# 09_LMS2_RF.net
KiCad netlist of a schematic drawn in Altium Designer
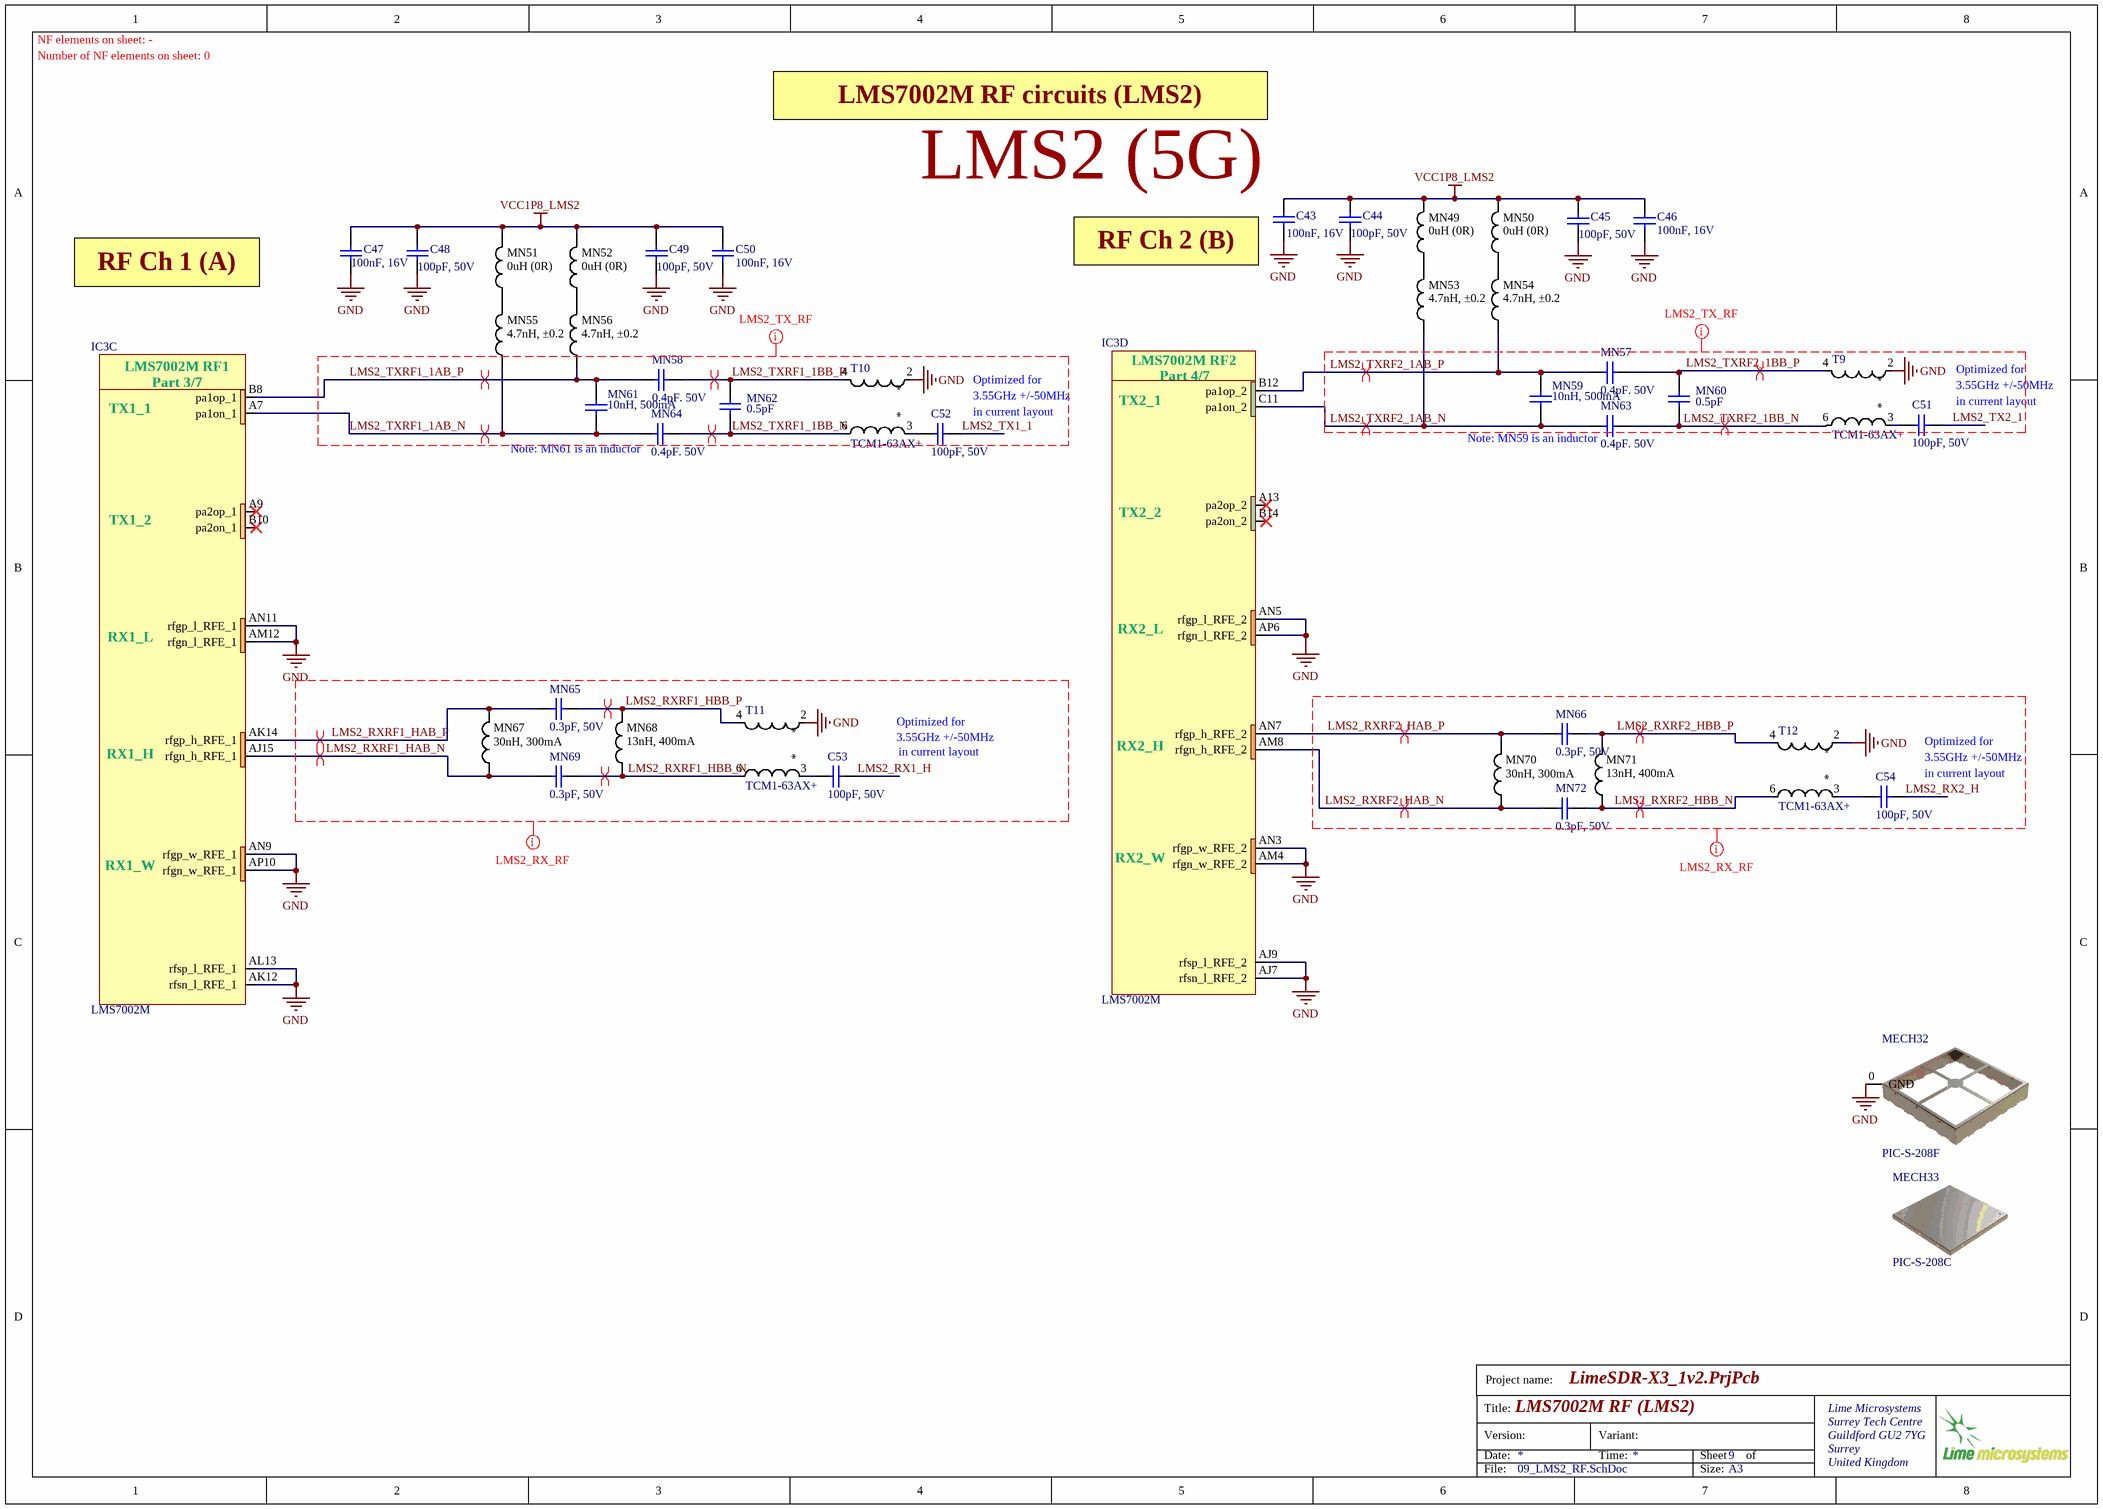
[diagram p0: 09_LMS2_RF.SchDoc]

(export (version "E")
  (design (tool "Eeschema 10.0.6"))
  (components
    (comp (ref "C43")
      (value "100nF, 16V")
      (footprint "CAP0402")
      (fields (field (name "MANUFACTURER") "Murata Electronics") (field (name "TOLERANCE") "10 %"))
      (libsource (lib "") (part "Cap_0402_7"))
    )
    (comp (ref "C44")
      (value "100pF, 50V")
      (footprint "CAP0402")
      (fields (field (name "MANUFACTURER") "Yageo") (field (name "TOLERANCE") "±5%"))
      (libsource (lib "") (part "Cap_0402_5"))
    )
    (comp (ref "C45")
      (value "100pF, 50V")
      (footprint "CAP0402")
      (fields (field (name "MANUFACTURER") "Yageo") (field (name "TOLERANCE") "±5%"))
      (libsource (lib "") (part "Cap_0402_5"))
    )
    (comp (ref "C46")
      (value "100nF, 16V")
      (footprint "CAP0402")
      (fields (field (name "MANUFACTURER") "Murata Electronics") (field (name "TOLERANCE") "10 %"))
      (libsource (lib "") (part "Cap_0402_7"))
    )
    (comp (ref "C47")
      (value "100nF, 16V")
      (footprint "CAP0402")
      (fields (field (name "MANUFACTURER") "Murata Electronics") (field (name "TOLERANCE") "10 %"))
      (libsource (lib "") (part "Cap_0402_6"))
    )
    (comp (ref "C48")
      (value "100pF, 50V")
      (footprint "CAP0402")
      (fields (field (name "MANUFACTURER") "Yageo") (field (name "TOLERANCE") "±5%"))
      (libsource (lib "") (part "Cap_0402_5"))
    )
    (comp (ref "C49")
      (value "100pF, 50V")
      (footprint "CAP0402")
      (fields (field (name "MANUFACTURER") "Yageo") (field (name "TOLERANCE") "±5%"))
      (libsource (lib "") (part "Cap_0402_5"))
    )
    (comp (ref "C50")
      (value "100nF, 16V")
      (footprint "CAP0402")
      (fields (field (name "MANUFACTURER") "Murata Electronics") (field (name "TOLERANCE") "10 %"))
      (libsource (lib "") (part "Cap_0402_6"))
    )
    (comp (ref "C51")
      (value "100pF, 50V")
      (footprint "CAP0402")
      (fields (field (name "TOLERANCE") "±5%") (field (name "MANUFACTURER") "Yageo"))
      (libsource (lib "") (part "Cap_0402_4"))
    )
    (comp (ref "C52")
      (value "100pF, 50V")
      (footprint "CAP0402")
      (fields (field (name "TOLERANCE") "±5%") (field (name "MANUFACTURER") "Yageo"))
      (libsource (lib "") (part "Cap_0402_4"))
    )
    (comp (ref "C53")
      (value "100pF, 50V")
      (footprint "CAP0402")
      (fields (field (name "TOLERANCE") "±5%") (field (name "MANUFACTURER") "Yageo"))
      (libsource (lib "LimeMicroAltiumLib_schLib") (part "Cap_0402"))
    )
    (comp (ref "C54")
      (value "100pF, 50V")
      (footprint "CAP0402")
      (fields (field (name "TOLERANCE") "±5%") (field (name "MANUFACTURER") "Yageo"))
      (libsource (lib "LimeMicroAltiumLib_schLib") (part "Cap_0402"))
    )
    (comp (ref "IC3")
      (value "LMS7002M")
      (footprint "LMS7002M_v5")
      (description "Schematic symbol revision 4. Default footprint - 0.31mm pad")
      (fields (field (name "MANUFACTURER") "Lime Microsystems"))
      (libsource (lib "LimeMicroAltiumLib_schLib_r04") (part "LMS7002Mr4"))
    )
    (comp (ref "MECH32")
      (value "PIC-S-208F")
      (footprint "PIC-S-208F_RF_SHIELD_FRAME_r0")
      (fields (field (name "MANUFACTURER") "3G Shielding Specialties LP"))
      (libsource (lib "LimeMicroAltiumLib") (part "PIC-S-208F_RF_SHIELD_FRAME"))
    )
    (comp (ref "MECH33")
      (value "PIC-S-208C")
      (footprint "PIC-S-208C_RF_SHIELD_COVER")
      (fields (field (name "MANUFACTURER") "3G Shielding Specialties LP"))
      (libsource (lib "LimeMicroAltiumLib") (part "PIC-S-208C_RF_SHIELD_COVER"))
    )
    (comp (ref "MN49")
      (value "0uH (0R)")
      (footprint "RES0603")
      (fields
        (field (name "MANUFACTURER") "Panasonic Electronic Components")
        (field (name "MANUFACTURER PART NUMBER") "ERJ-3GEY0R00V")
        (field (name "TOLERANCE") "Jumper")
      )
      (libsource (lib "LimeMicroAltiumLib_schLib") (part "Inductor_0603"))
    )
    (comp (ref "MN50")
      (value "0uH (0R)")
      (footprint "RES0603")
      (fields
        (field (name "MANUFACTURER") "Panasonic Electronic Components")
        (field (name "MANUFACTURER PART NUMBER") "ERJ-3GEY0R00V")
        (field (name "TOLERANCE") "Jumper")
      )
      (libsource (lib "LimeMicroAltiumLib_schLib") (part "Inductor_0603"))
    )
    (comp (ref "MN51")
      (value "0uH (0R)")
      (footprint "RES0603")
      (fields
        (field (name "MANUFACTURER") "Panasonic Electronic Components")
        (field (name "MANUFACTURER PART NUMBER") "ERJ-3GEY0R00V")
        (field (name "TOLERANCE") "Jumper")
      )
      (libsource (lib "LimeMicroAltiumLib_schLib") (part "Inductor_0603"))
    )
    (comp (ref "MN52")
      (value "0uH (0R)")
      (footprint "RES0603")
      (fields
        (field (name "MANUFACTURER") "Panasonic Electronic Components")
        (field (name "MANUFACTURER PART NUMBER") "ERJ-3GEY0R00V")
        (field (name "TOLERANCE") "Jumper")
      )
      (libsource (lib "LimeMicroAltiumLib_schLib") (part "Inductor_0603"))
    )
    (comp (ref "MN53")
      (value "4.7nH, ±0.2")
      (footprint "RES0402")
      (fields (field (name "MANUFACTURER") "Murata"))
      (libsource (lib "LimeMicroAltiumLib_schLib") (part "Inductor_0603"))
    )
    (comp (ref "MN54")
      (value "4.7nH, ±0.2")
      (footprint "RES0402")
      (fields (field (name "MANUFACTURER") "Murata"))
      (libsource (lib "LimeMicroAltiumLib_schLib") (part "Inductor_0603"))
    )
    (comp (ref "MN55")
      (value "4.7nH, ±0.2")
      (footprint "RES0402")
      (fields (field (name "MANUFACTURER") "Murata"))
      (libsource (lib "LimeMicroAltiumLib_schLib") (part "Inductor_0603"))
    )
    (comp (ref "MN56")
      (value "4.7nH, ±0.2")
      (footprint "RES0402")
      (fields (field (name "MANUFACTURER") "Murata"))
      (libsource (lib "LimeMicroAltiumLib_schLib") (part "Inductor_0603"))
    )
    (comp (ref "MN57")
      (value "0.4pF. 50V")
      (footprint "CAP0402")
      (fields (field (name "MANUFACTURER") "Murata"))
      (libsource (lib "") (part "Cap_0402_3"))
    )
    (comp (ref "MN58")
      (value "0.4pF. 50V")
      (footprint "CAP0402")
      (fields (field (name "MANUFACTURER") "Murata"))
      (libsource (lib "") (part "Cap_0402_3"))
    )
    (comp (ref "MN59")
      (value "10nH, 500mA")
      (footprint "CAP0402")
      (fields (field (name "MANUFACTURER") "Murata") (field (name "TOLERANCE") "2%"))
      (libsource (lib "") (part "Cap_0402_1"))
    )
    (comp (ref "MN60")
      (value "0.5pF")
      (footprint "CAP0402")
      (fields (field (name "TOLERANCE") "±0.25pF") (field (name "MANUFACTURER") "Yageo"))
      (libsource (lib "") (part "Cap_0402_4"))
    )
    (comp (ref "MN61")
      (value "10nH, 500mA")
      (footprint "CAP0402")
      (fields (field (name "MANUFACTURER") "Murata") (field (name "TOLERANCE") "2%"))
      (libsource (lib "") (part "Cap_0402_1"))
    )
    (comp (ref "MN62")
      (value "0.5pF")
      (footprint "CAP0402")
      (fields (field (name "TOLERANCE") "±0.25pF") (field (name "MANUFACTURER") "Yageo"))
      (libsource (lib "") (part "Cap_0402_4"))
    )
    (comp (ref "MN63")
      (value "0.4pF. 50V")
      (footprint "CAP0402")
      (fields (field (name "MANUFACTURER") "Murata"))
      (libsource (lib "") (part "Cap_0402_2"))
    )
    (comp (ref "MN64")
      (value "0.4pF. 50V")
      (footprint "CAP0402")
      (fields (field (name "MANUFACTURER") "Murata"))
      (libsource (lib "") (part "Cap_0402_2"))
    )
    (comp (ref "MN65")
      (value "0.3pF, 50V")
      (footprint "CAP0402")
      (fields (field (name "MANUFACTURER") "Johanson"))
      (libsource (lib "") (part "Cap_0402_3"))
    )
    (comp (ref "MN66")
      (value "0.3pF, 50V")
      (footprint "CAP0402")
      (fields (field (name "MANUFACTURER") "Johanson"))
      (libsource (lib "") (part "Cap_0402_3"))
    )
    (comp (ref "MN67")
      (value "30nH, 300mA")
      (footprint "RES0402")
      (fields (field (name "MANUFACTURER") "TDK") (field (name "TOLERANCE") "5%"))
      (libsource (lib "") (part "Inductor_0603_2"))
    )
    (comp (ref "MN68")
      (value "13nH, 400mA")
      (footprint "RES0402")
      (fields (field (name "MANUFACTURER") "TDK") (field (name "TOLERANCE") "5%"))
      (libsource (lib "") (part "Inductor_0603_1"))
    )
    (comp (ref "MN69")
      (value "0.3pF, 50V")
      (footprint "CAP0402")
      (fields (field (name "MANUFACTURER") "Johanson"))
      (libsource (lib "") (part "Cap_0402_3"))
    )
    (comp (ref "MN70")
      (value "30nH, 300mA")
      (footprint "RES0402")
      (fields (field (name "MANUFACTURER") "TDK") (field (name "TOLERANCE") "5%"))
      (libsource (lib "") (part "Inductor_0603_2"))
    )
    (comp (ref "MN71")
      (value "13nH, 400mA")
      (footprint "RES0402")
      (fields (field (name "MANUFACTURER") "TDK") (field (name "TOLERANCE") "5%"))
      (libsource (lib "") (part "Inductor_0603_1"))
    )
    (comp (ref "MN72")
      (value "0.3pF, 50V")
      (footprint "CAP0402")
      (fields (field (name "MANUFACTURER") "Johanson"))
      (libsource (lib "") (part "Cap_0402_3"))
    )
    (comp (ref "T9")
      (value "TCM1-63AX+")
      (footprint "TCM1-63AX+_v2")
      (fields (field (name "MANUFACTURER") "Mini-circuits"))
      (libsource (lib "LimeMicroAltiumLib_schLib") (part "Balun_v2"))
    )
    (comp (ref "T10")
      (value "TCM1-63AX+")
      (footprint "TCM1-63AX+_v2")
      (fields (field (name "MANUFACTURER") "Mini-circuits"))
      (libsource (lib "LimeMicroAltiumLib_schLib") (part "Balun_v2"))
    )
    (comp (ref "T11")
      (value "TCM1-63AX+")
      (footprint "TCM1-63AX+_v2")
      (fields (field (name "MANUFACTURER") "Mini-circuits"))
      (libsource (lib "") (part "Balun_v2_1"))
    )
    (comp (ref "T12")
      (value "TCM1-63AX+")
      (footprint "TCM1-63AX+_v2")
      (fields (field (name "MANUFACTURER") "Mini-circuits"))
      (libsource (lib "") (part "Balun_v2_1"))
    )
  )
  (nets
    (net (code "1") (name "/LMS2_RX1_H") (class "Default")
      (node (ref "C53") (pin "1") (pinfunction "1_1") (pintype "passive"))
    )
    (net (code "2") (name "/LMS2_RX2_H") (class "Default")
      (node (ref "C54") (pin "1") (pinfunction "1_1") (pintype "passive"))
    )
    (net (code "3") (name "/LMS2_RXRF1_HAB_N") (class "Default")
      (node (ref "IC3") (pin "AJ15") (pinfunction "rfgn_h_RFE_1_AJ15") (pintype "passive"))
      (node (ref "MN67") (pin "1") (pinfunction "1_1") (pintype "passive"))
      (node (ref "MN69") (pin "2") (pinfunction "2_2") (pintype "passive"))
    )
    (net (code "4") (name "/LMS2_RXRF1_HAB_P") (class "Default")
      (node (ref "IC3") (pin "AK14") (pinfunction "rfgp_h_RFE_1_AK14") (pintype "passive"))
      (node (ref "MN65") (pin "2") (pinfunction "2_2") (pintype "passive"))
      (node (ref "MN67") (pin "2") (pinfunction "2_2") (pintype "passive"))
    )
    (net (code "5") (name "/LMS2_RXRF1_HBB_N") (class "Default")
      (node (ref "MN68") (pin "1") (pinfunction "1_1") (pintype "passive"))
      (node (ref "MN69") (pin "1") (pinfunction "1_1") (pintype "passive"))
      (node (ref "T11") (pin "6") (pinfunction "6_6") (pintype "passive"))
    )
    (net (code "6") (name "/LMS2_RXRF1_HBB_P") (class "Default")
      (node (ref "MN65") (pin "1") (pinfunction "1_1") (pintype "passive"))
      (node (ref "MN68") (pin "2") (pinfunction "2_2") (pintype "passive"))
      (node (ref "T11") (pin "4") (pinfunction "4_4") (pintype "passive"))
    )
    (net (code "7") (name "/LMS2_RXRF2_HAB_N") (class "Default")
      (node (ref "IC3") (pin "AM8") (pinfunction "rfgn_h_RFE_2_AM8") (pintype "passive"))
      (node (ref "MN70") (pin "1") (pinfunction "1_1") (pintype "passive"))
      (node (ref "MN72") (pin "2") (pinfunction "2_2") (pintype "passive"))
    )
    (net (code "8") (name "/LMS2_RXRF2_HAB_P") (class "Default")
      (node (ref "IC3") (pin "AN7") (pinfunction "rfgp_h_RFE_2_AN7") (pintype "passive"))
      (node (ref "MN66") (pin "2") (pinfunction "2_2") (pintype "passive"))
      (node (ref "MN70") (pin "2") (pinfunction "2_2") (pintype "passive"))
    )
    (net (code "9") (name "/LMS2_RXRF2_HBB_N") (class "Default")
      (node (ref "MN71") (pin "1") (pinfunction "1_1") (pintype "passive"))
      (node (ref "MN72") (pin "1") (pinfunction "1_1") (pintype "passive"))
      (node (ref "T12") (pin "6") (pinfunction "6_6") (pintype "passive"))
    )
    (net (code "10") (name "/LMS2_RXRF2_HBB_P") (class "Default")
      (node (ref "MN66") (pin "1") (pinfunction "1_1") (pintype "passive"))
      (node (ref "MN71") (pin "2") (pinfunction "2_2") (pintype "passive"))
      (node (ref "T12") (pin "4") (pinfunction "4_4") (pintype "passive"))
    )
    (net (code "11") (name "/LMS2_TX1_1") (class "Default")
      (node (ref "C52") (pin "1") (pinfunction "1_1") (pintype "passive"))
    )
    (net (code "12") (name "/LMS2_TX2_1") (class "Default")
      (node (ref "C51") (pin "1") (pinfunction "1_1") (pintype "passive"))
    )
    (net (code "13") (name "/LMS2_TXRF1_1AB_N") (class "Default")
      (node (ref "IC3") (pin "A7") (pinfunction "pa1on_1_A7") (pintype "passive"))
      (node (ref "MN55") (pin "1") (pinfunction "1_1") (pintype "passive"))
      (node (ref "MN61") (pin "2") (pinfunction "2_2") (pintype "passive"))
      (node (ref "MN64") (pin "2") (pinfunction "2_2") (pintype "passive"))
    )
    (net (code "14") (name "/LMS2_TXRF1_1AB_P") (class "Default")
      (node (ref "IC3") (pin "B8") (pinfunction "pa1op_1_B8") (pintype "passive"))
      (node (ref "MN56") (pin "1") (pinfunction "1_1") (pintype "passive"))
      (node (ref "MN58") (pin "2") (pinfunction "2_2") (pintype "passive"))
      (node (ref "MN61") (pin "1") (pinfunction "1_1") (pintype "passive"))
    )
    (net (code "15") (name "/LMS2_TXRF1_1BB_N") (class "Default")
      (node (ref "MN62") (pin "1") (pinfunction "1_1") (pintype "passive"))
      (node (ref "MN64") (pin "1") (pinfunction "1_1") (pintype "passive"))
      (node (ref "T10") (pin "6") (pinfunction "6_6") (pintype "passive"))
    )
    (net (code "16") (name "/LMS2_TXRF1_1BB_P") (class "Default")
      (node (ref "MN58") (pin "1") (pinfunction "1_1") (pintype "passive"))
      (node (ref "MN62") (pin "2") (pinfunction "2_2") (pintype "passive"))
      (node (ref "T10") (pin "4") (pinfunction "4_4") (pintype "passive"))
    )
    (net (code "17") (name "/LMS2_TXRF2_1AB_N") (class "Default")
      (node (ref "IC3") (pin "C11") (pinfunction "pa1on_2_C11") (pintype "passive"))
      (node (ref "MN53") (pin "1") (pinfunction "1_1") (pintype "passive"))
      (node (ref "MN59") (pin "2") (pinfunction "2_2") (pintype "passive"))
      (node (ref "MN63") (pin "2") (pinfunction "2_2") (pintype "passive"))
    )
    (net (code "18") (name "/LMS2_TXRF2_1AB_P") (class "Default")
      (node (ref "IC3") (pin "B12") (pinfunction "pa1op_2_B12") (pintype "passive"))
      (node (ref "MN54") (pin "1") (pinfunction "1_1") (pintype "passive"))
      (node (ref "MN57") (pin "2") (pinfunction "2_2") (pintype "passive"))
      (node (ref "MN59") (pin "1") (pinfunction "1_1") (pintype "passive"))
    )
    (net (code "19") (name "/LMS2_TXRF2_1BB_N") (class "Default")
      (node (ref "MN60") (pin "1") (pinfunction "1_1") (pintype "passive"))
      (node (ref "MN63") (pin "1") (pinfunction "1_1") (pintype "passive"))
      (node (ref "T9") (pin "6") (pinfunction "6_6") (pintype "passive"))
    )
    (net (code "20") (name "/LMS2_TXRF2_1BB_P") (class "Default")
      (node (ref "MN57") (pin "1") (pinfunction "1_1") (pintype "passive"))
      (node (ref "MN60") (pin "2") (pinfunction "2_2") (pintype "passive"))
      (node (ref "T9") (pin "4") (pinfunction "4_4") (pintype "passive"))
    )
    (net (code "21") (name "GND") (class "Default")
      (node (ref "C43") (pin "1") (pinfunction "1_1") (pintype "passive"))
      (node (ref "C44") (pin "1") (pinfunction "1_1") (pintype "passive"))
      (node (ref "C45") (pin "1") (pinfunction "1_1") (pintype "passive"))
      (node (ref "C46") (pin "1") (pinfunction "1_1") (pintype "passive"))
      (node (ref "C47") (pin "1") (pinfunction "1_1") (pintype "passive"))
      (node (ref "C48") (pin "1") (pinfunction "1_1") (pintype "passive"))
      (node (ref "C49") (pin "1") (pinfunction "1_1") (pintype "passive"))
      (node (ref "C50") (pin "1") (pinfunction "1_1") (pintype "passive"))
      (node (ref "IC3") (pin "AJ7") (pinfunction "rfsn_l_RFE_2_AJ7") (pintype "passive"))
      (node (ref "IC3") (pin "AJ9") (pinfunction "rfsp_l_RFE_2_AJ9") (pintype "passive"))
      (node (ref "IC3") (pin "AK12") (pinfunction "rfsn_l_RFE_1_AK12") (pintype "passive"))
      (node (ref "IC3") (pin "AL13") (pinfunction "rfsp_l_RFE_1_AL13") (pintype "passive"))
      (node (ref "IC3") (pin "AM12") (pinfunction "rfgn_l_RFE_1_AM12") (pintype "passive"))
      (node (ref "IC3") (pin "AM4") (pinfunction "rfgn_w_RFE_2_AM4") (pintype "passive"))
      (node (ref "IC3") (pin "AN11") (pinfunction "rfgp_l_RFE_1_AN11") (pintype "passive"))
      (node (ref "IC3") (pin "AN3") (pinfunction "rfgp_w_RFE_2_AN3") (pintype "passive"))
      (node (ref "IC3") (pin "AN5") (pinfunction "rfgp_l_RFE_2_AN5") (pintype "passive"))
      (node (ref "IC3") (pin "AN9") (pinfunction "rfgp_w_RFE_1_AN9") (pintype "passive"))
      (node (ref "IC3") (pin "AP10") (pinfunction "rfgn_w_RFE_1_AP10") (pintype "passive"))
      (node (ref "IC3") (pin "AP6") (pinfunction "rfgn_l_RFE_2_AP6") (pintype "passive"))
      (node (ref "MECH32") (pin "0") (pinfunction "GND_0") (pintype "passive"))
      (node (ref "T10") (pin "2") (pinfunction "2_2") (pintype "passive"))
      (node (ref "T11") (pin "2") (pinfunction "2_2") (pintype "passive"))
      (node (ref "T12") (pin "2") (pinfunction "2_2") (pintype "passive"))
      (node (ref "T9") (pin "2") (pinfunction "2_2") (pintype "passive"))
    )
    (net (code "22") (name "Net-(C51-Pad2)") (class "Default")
      (node (ref "C51") (pin "2") (pinfunction "2_2") (pintype "passive"))
      (node (ref "T9") (pin "3") (pinfunction "3_3") (pintype "passive"))
    )
    (net (code "23") (name "Net-(C52-Pad2)") (class "Default")
      (node (ref "C52") (pin "2") (pinfunction "2_2") (pintype "passive"))
      (node (ref "T10") (pin "3") (pinfunction "3_3") (pintype "passive"))
    )
    (net (code "24") (name "Net-(C53-Pad2)") (class "Default")
      (node (ref "C53") (pin "2") (pinfunction "2_2") (pintype "passive"))
      (node (ref "T11") (pin "3") (pinfunction "3_3") (pintype "passive"))
    )
    (net (code "25") (name "Net-(C54-Pad2)") (class "Default")
      (node (ref "C54") (pin "2") (pinfunction "2_2") (pintype "passive"))
      (node (ref "T12") (pin "3") (pinfunction "3_3") (pintype "passive"))
    )
    (net (code "26") (name "Net-(MN49-Pad1)") (class "Default")
      (node (ref "MN49") (pin "1") (pinfunction "1_1") (pintype "passive"))
      (node (ref "MN53") (pin "2") (pinfunction "2_2") (pintype "passive"))
    )
    (net (code "27") (name "Net-(MN50-Pad1)") (class "Default")
      (node (ref "MN50") (pin "1") (pinfunction "1_1") (pintype "passive"))
      (node (ref "MN54") (pin "2") (pinfunction "2_2") (pintype "passive"))
    )
    (net (code "28") (name "Net-(MN51-Pad1)") (class "Default")
      (node (ref "MN51") (pin "1") (pinfunction "1_1") (pintype "passive"))
      (node (ref "MN55") (pin "2") (pinfunction "2_2") (pintype "passive"))
    )
    (net (code "29") (name "Net-(MN52-Pad1)") (class "Default")
      (node (ref "MN52") (pin "1") (pinfunction "1_1") (pintype "passive"))
      (node (ref "MN56") (pin "2") (pinfunction "2_2") (pintype "passive"))
    )
    (net (code "30") (name "VCC1P8_LMS2") (class "Default")
      (node (ref "C43") (pin "2") (pinfunction "2_2") (pintype "passive"))
      (node (ref "C44") (pin "2") (pinfunction "2_2") (pintype "passive"))
      (node (ref "C45") (pin "2") (pinfunction "2_2") (pintype "passive"))
      (node (ref "C46") (pin "2") (pinfunction "2_2") (pintype "passive"))
      (node (ref "C47") (pin "2") (pinfunction "2_2") (pintype "passive"))
      (node (ref "C48") (pin "2") (pinfunction "2_2") (pintype "passive"))
      (node (ref "C49") (pin "2") (pinfunction "2_2") (pintype "passive"))
      (node (ref "C50") (pin "2") (pinfunction "2_2") (pintype "passive"))
      (node (ref "MN49") (pin "2") (pinfunction "2_2") (pintype "passive"))
      (node (ref "MN50") (pin "2") (pinfunction "2_2") (pintype "passive"))
      (node (ref "MN51") (pin "2") (pinfunction "2_2") (pintype "passive"))
      (node (ref "MN52") (pin "2") (pinfunction "2_2") (pintype "passive"))
    )
    (net (code "31") (name "unconnected-(IC3C-pa2on_1-PadB10)") (class "Default")
      (node (ref "IC3") (pin "B10") (pinfunction "pa2on_1_B10") (pintype "passive+no_connect"))
    )
    (net (code "32") (name "unconnected-(IC3C-pa2op_1-PadA9)") (class "Default")
      (node (ref "IC3") (pin "A9") (pinfunction "pa2op_1_A9") (pintype "passive+no_connect"))
    )
    (net (code "33") (name "unconnected-(IC3D-pa2on_2-PadB14)") (class "Default")
      (node (ref "IC3") (pin "B14") (pinfunction "pa2on_2_B14") (pintype "passive+no_connect"))
    )
    (net (code "34") (name "unconnected-(IC3D-pa2op_2-PadA13)") (class "Default")
      (node (ref "IC3") (pin "A13") (pinfunction "pa2op_2_A13") (pintype "passive+no_connect"))
    )
  )
)
